# Power_Amp_carlos.net
KiCad netlist of a schematic drawn in EAGLE
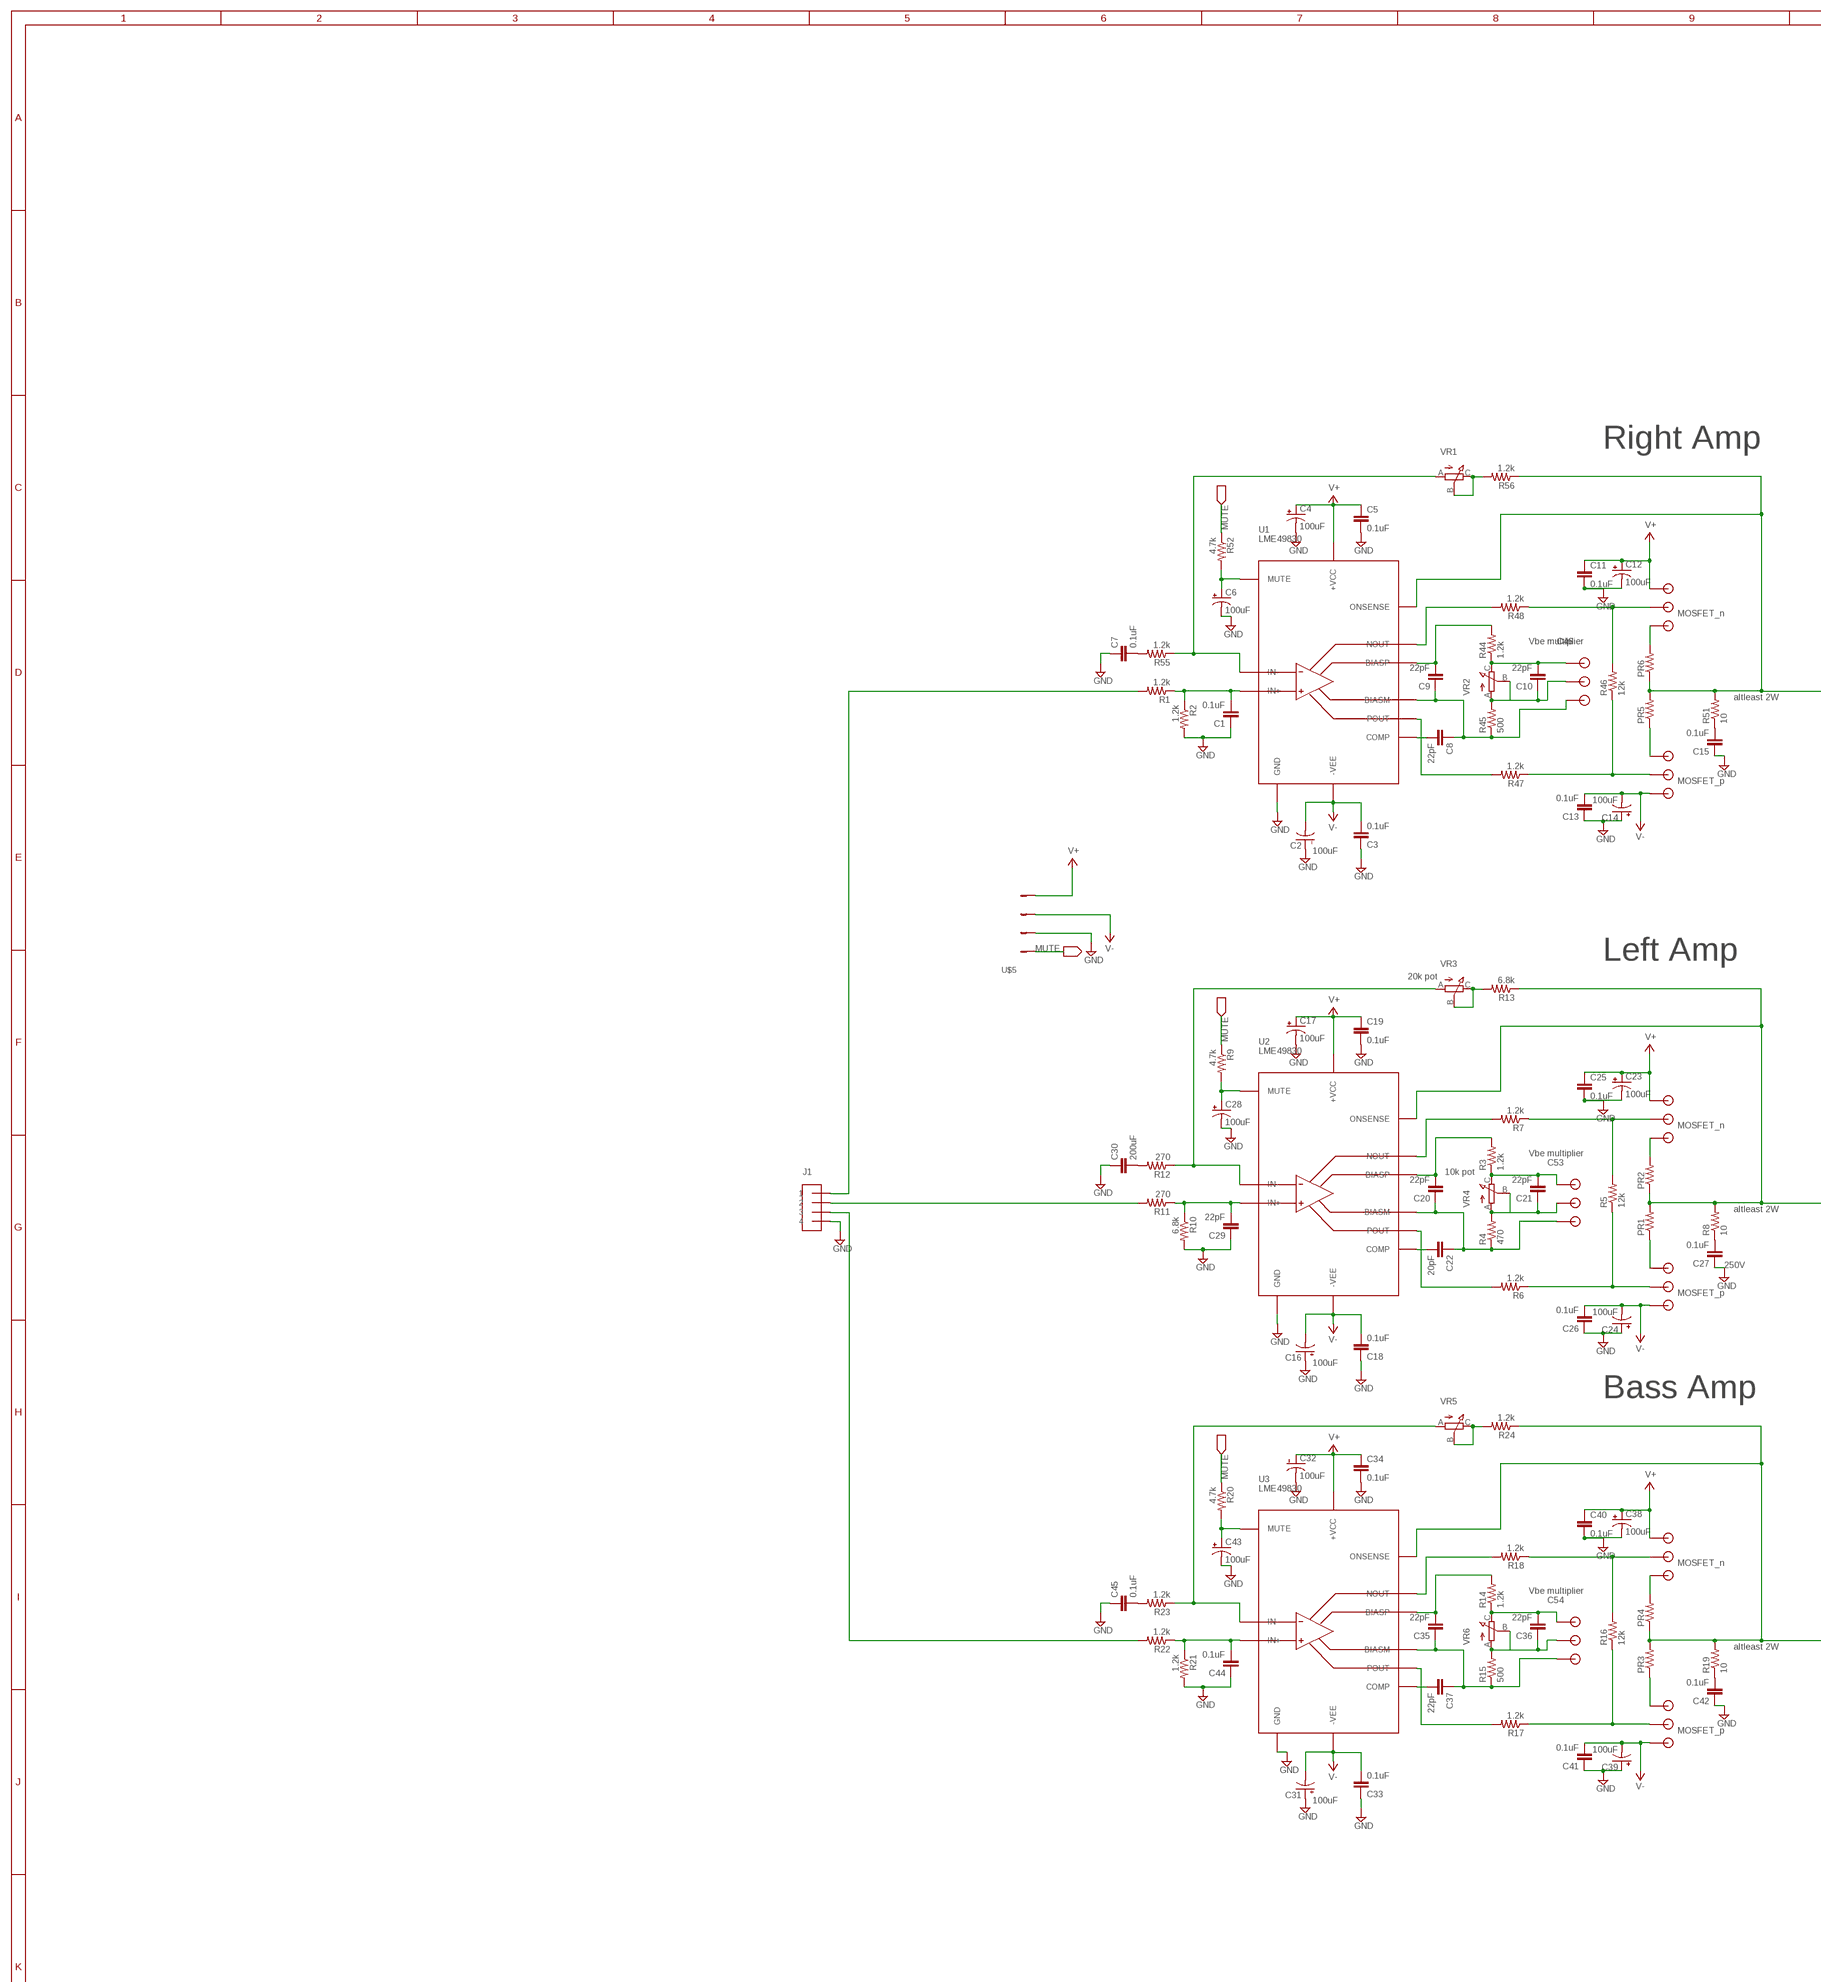
[diagram p0: schematic, sheet 1, part 1 of 3]
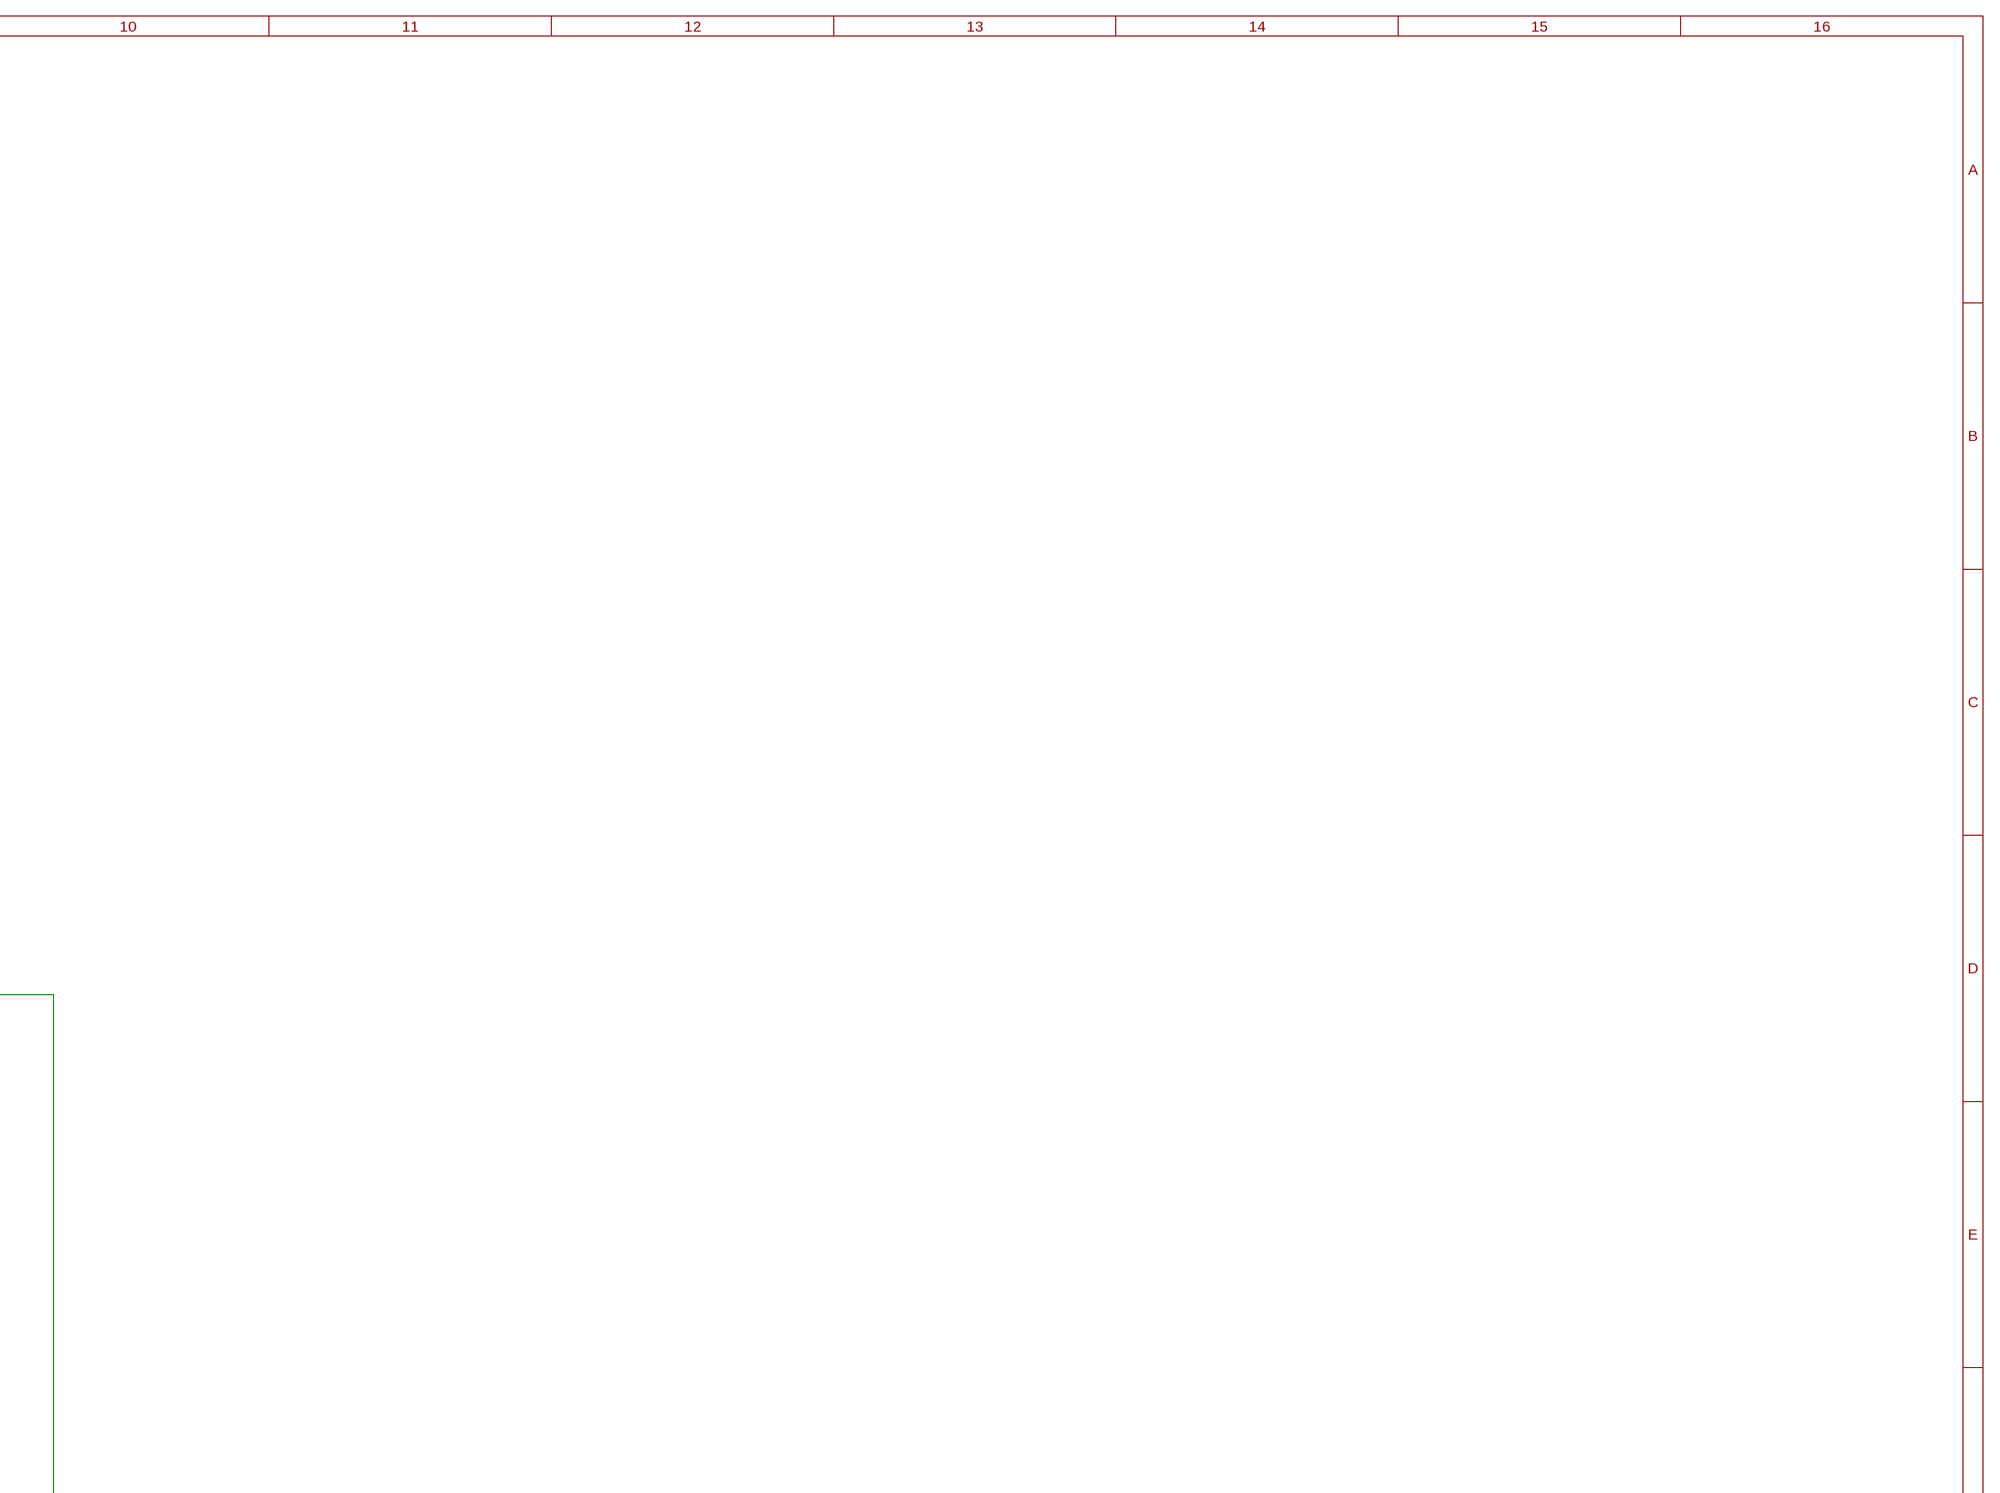
[diagram p1: schematic, sheet 1, part 2 of 3]
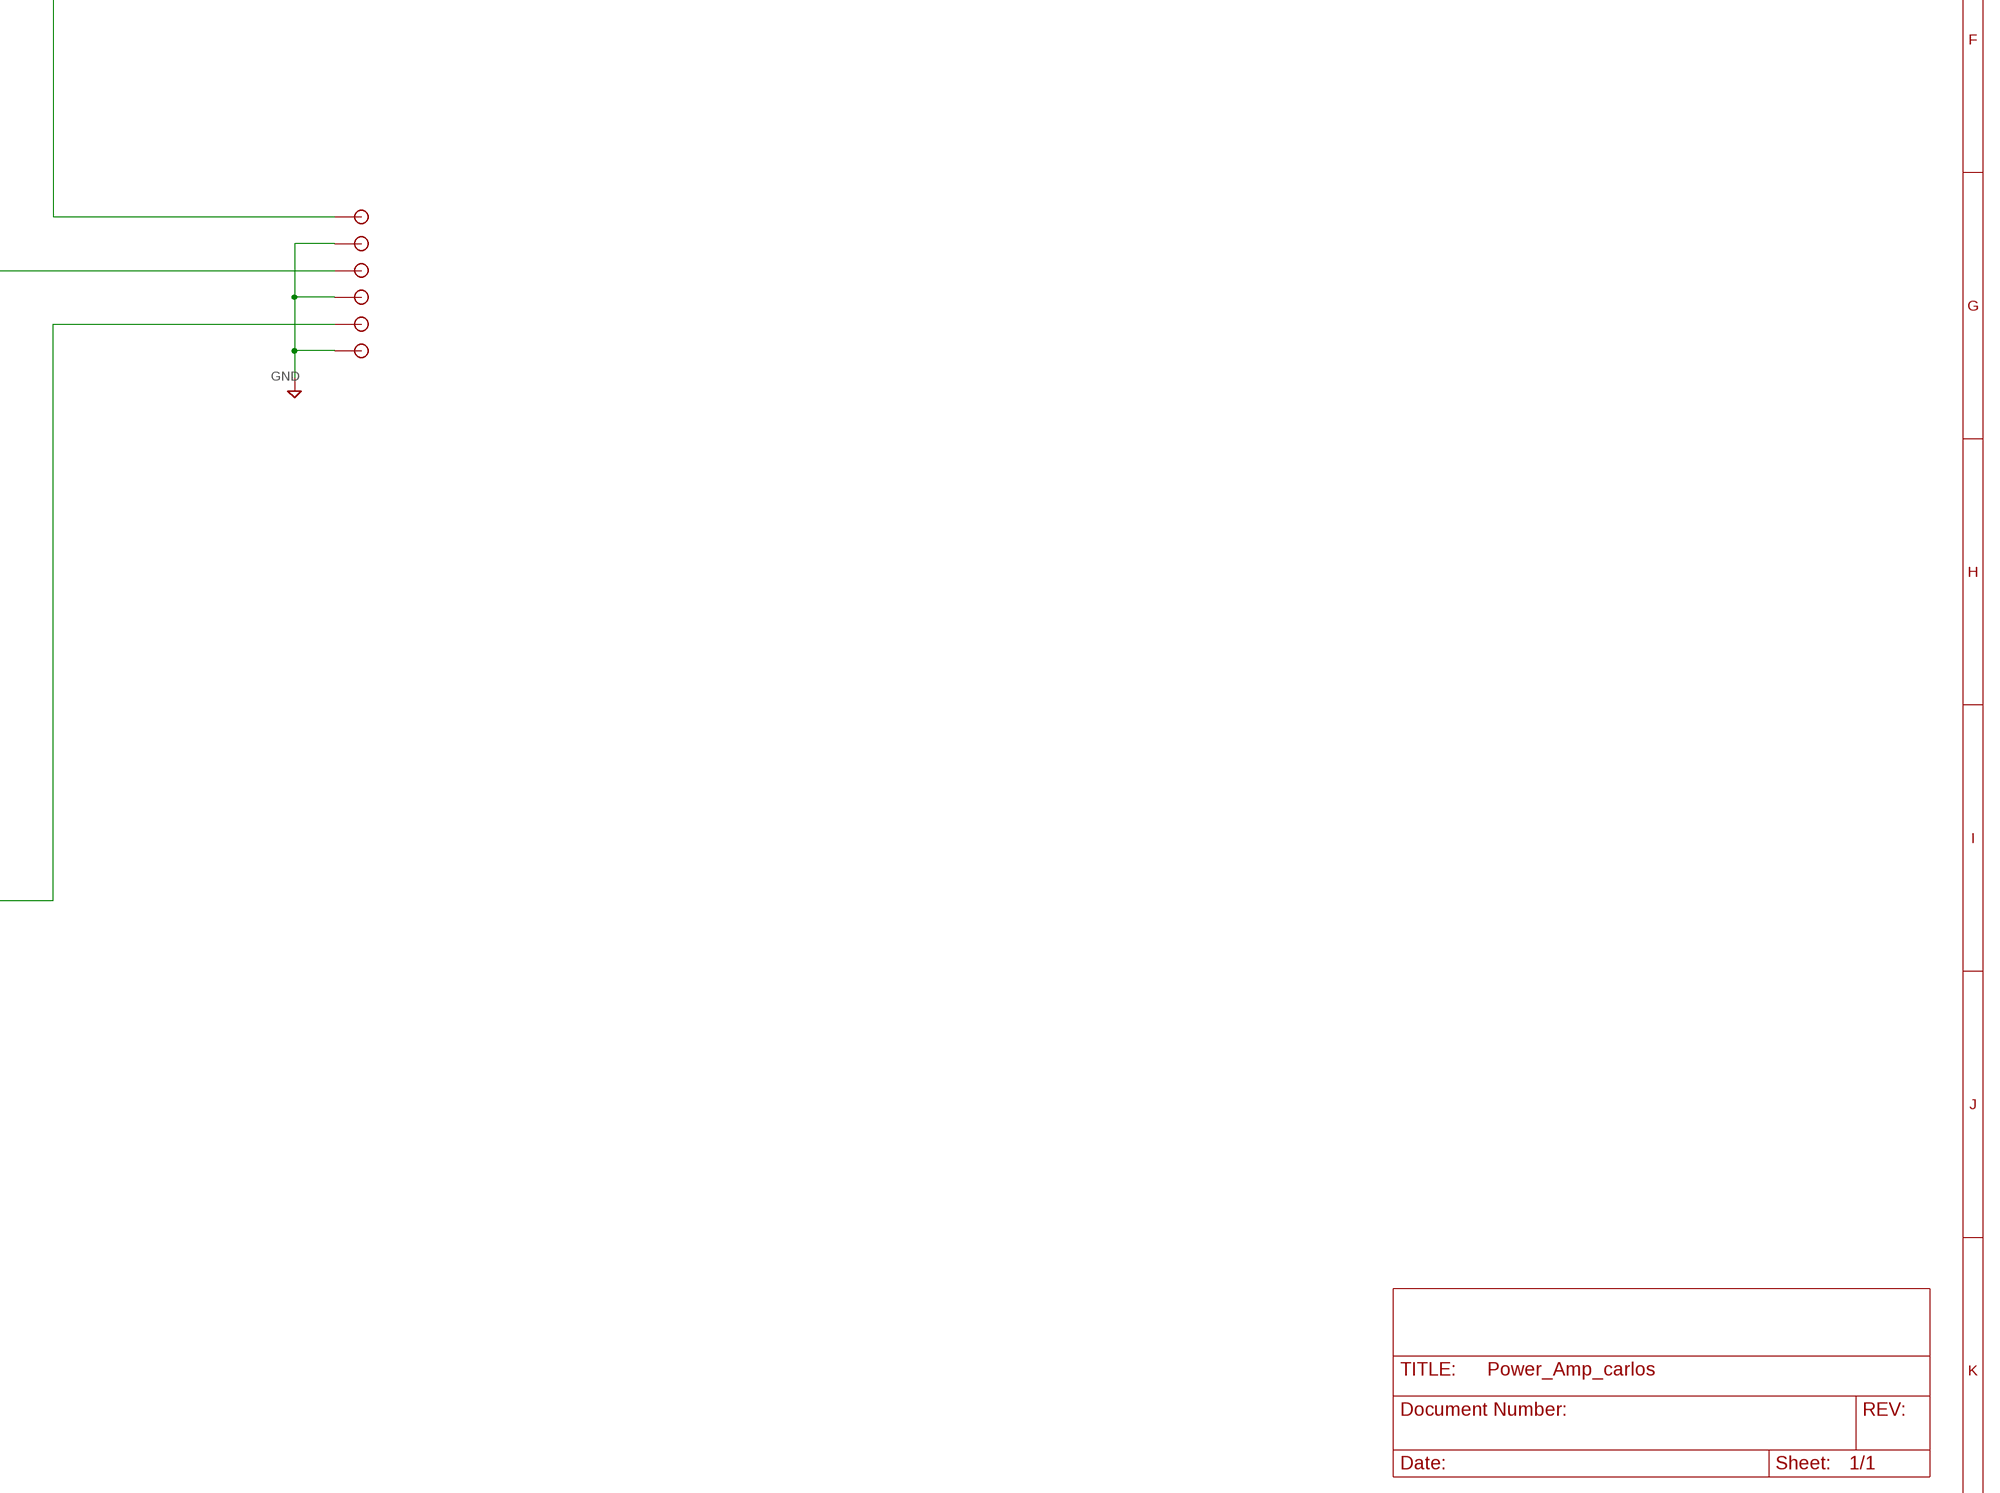
[diagram p2: schematic, sheet 1, part 3 of 3]

(export (version "E")
  (design (tool "Eeschema 10.0.6"))
  (components
    (comp (ref "C1")
      (value "0.1uF")
      (footprint "eagle-import:C050-024X044")
      (libsource (lib "eagle-import") (part "C-EU050-024X044"))
    )
    (comp (ref "C2")
      (value "100uF")
      (footprint "eagle-import:E2,5-6")
      (libsource (lib "eagle-import") (part "CPOL-USE2.5-6"))
    )
    (comp (ref "C3")
      (value "0.1uF")
      (footprint "eagle-import:C050-024X044")
      (libsource (lib "eagle-import") (part "C-EU050-024X044"))
    )
    (comp (ref "C4")
      (value "100uF")
      (footprint "eagle-import:E2,5-6")
      (libsource (lib "eagle-import") (part "CPOL-USE2.5-6"))
    )
    (comp (ref "C5")
      (value "0.1uF")
      (footprint "eagle-import:C050-024X044")
      (libsource (lib "eagle-import") (part "C-EU050-024X044"))
    )
    (comp (ref "C6")
      (value "100uF")
      (footprint "eagle-import:E2,5-6")
      (libsource (lib "eagle-import") (part "CPOL-USE2.5-6"))
    )
    (comp (ref "C7")
      (value "0.1uF")
      (footprint "eagle-import:C050-024X044")
      (libsource (lib "eagle-import") (part "C-EU050-024X044"))
    )
    (comp (ref "C8")
      (value "22pF")
      (footprint "eagle-import:C050-024X044")
      (libsource (lib "eagle-import") (part "C-EU050-024X044"))
    )
    (comp (ref "C9")
      (value "22pF")
      (footprint "eagle-import:C050-024X044")
      (libsource (lib "eagle-import") (part "C-EU050-024X044"))
    )
    (comp (ref "C10")
      (value "22pF")
      (footprint "eagle-import:C050-024X044")
      (libsource (lib "eagle-import") (part "C-EU050-024X044"))
    )
    (comp (ref "C11")
      (value "0.1uF")
      (footprint "eagle-import:C050-024X044")
      (libsource (lib "eagle-import") (part "C-EU050-024X044"))
    )
    (comp (ref "C12")
      (value "100uF")
      (footprint "eagle-import:E2,5-6")
      (libsource (lib "eagle-import") (part "CPOL-USE2.5-6"))
    )
    (comp (ref "C13")
      (value "0.1uF")
      (footprint "eagle-import:C050-024X044")
      (libsource (lib "eagle-import") (part "C-EU050-024X044"))
    )
    (comp (ref "C14")
      (value "100uF")
      (footprint "eagle-import:E2,5-6")
      (libsource (lib "eagle-import") (part "CPOL-USE2.5-6"))
    )
    (comp (ref "C15")
      (value "0.1uF")
      (footprint "eagle-import:C050-024X044")
      (libsource (lib "eagle-import") (part "C-EU050-024X044"))
    )
    (comp (ref "C16")
      (value "100uF")
      (footprint "eagle-import:E2,5-6")
      (libsource (lib "eagle-import") (part "CPOL-USE2.5-6"))
    )
    (comp (ref "C17")
      (value "100uF")
      (footprint "eagle-import:E2,5-6")
      (libsource (lib "eagle-import") (part "CPOL-USE2.5-6"))
    )
    (comp (ref "C18")
      (value "0.1uF")
      (footprint "eagle-import:C050-024X044")
      (libsource (lib "eagle-import") (part "C-EU050-024X044"))
    )
    (comp (ref "C19")
      (value "0.1uF")
      (footprint "eagle-import:C050-024X044")
      (libsource (lib "eagle-import") (part "C-EU050-024X044"))
    )
    (comp (ref "C20")
      (value "22pF")
      (footprint "eagle-import:C050-024X044")
      (libsource (lib "eagle-import") (part "C-EU050-024X044"))
    )
    (comp (ref "C21")
      (value "22pF")
      (footprint "eagle-import:C050-024X044")
      (libsource (lib "eagle-import") (part "C-EU050-024X044"))
    )
    (comp (ref "C22")
      (value "20pF")
      (footprint "eagle-import:C050-024X044")
      (libsource (lib "eagle-import") (part "C-EU050-024X044"))
    )
    (comp (ref "C23")
      (value "100uF")
      (footprint "eagle-import:E2,5-6")
      (libsource (lib "eagle-import") (part "CPOL-USE2.5-6"))
    )
    (comp (ref "C24")
      (value "100uF")
      (footprint "eagle-import:E2,5-6")
      (libsource (lib "eagle-import") (part "CPOL-USE2.5-6"))
    )
    (comp (ref "C25")
      (value "0.1uF")
      (footprint "eagle-import:C050-024X044")
      (libsource (lib "eagle-import") (part "C-EU050-024X044"))
    )
    (comp (ref "C26")
      (value "0.1uF")
      (footprint "eagle-import:C050-024X044")
      (libsource (lib "eagle-import") (part "C-EU050-024X044"))
    )
    (comp (ref "C27")
      (value "0.1uF")
      (footprint "eagle-import:C050-024X044")
      (libsource (lib "eagle-import") (part "C-EU050-024X044"))
    )
    (comp (ref "C28")
      (value "100uF")
      (footprint "eagle-import:E2,5-6")
      (libsource (lib "eagle-import") (part "CPOL-USE2.5-6"))
    )
    (comp (ref "C29")
      (value "22pF")
      (footprint "eagle-import:C050-024X044")
      (libsource (lib "eagle-import") (part "C-EU050-024X044"))
    )
    (comp (ref "C30")
      (value "200uF")
      (footprint "eagle-import:C050-024X044")
      (libsource (lib "eagle-import") (part "C-EU050-024X044"))
    )
    (comp (ref "C31")
      (value "100uF")
      (footprint "eagle-import:E2,5-6")
      (libsource (lib "eagle-import") (part "CPOL-USE2.5-6"))
    )
    (comp (ref "C32")
      (value "100uF")
      (footprint "eagle-import:E2,5-6")
      (libsource (lib "eagle-import") (part "CPOL-USE2.5-6"))
    )
    (comp (ref "C33")
      (value "0.1uF")
      (footprint "eagle-import:C050-024X044")
      (libsource (lib "eagle-import") (part "C-EU050-024X044"))
    )
    (comp (ref "C34")
      (value "0.1uF")
      (footprint "eagle-import:C050-024X044")
      (libsource (lib "eagle-import") (part "C-EU050-024X044"))
    )
    (comp (ref "C35")
      (value "22pF")
      (footprint "eagle-import:C050-024X044")
      (libsource (lib "eagle-import") (part "C-EU050-024X044"))
    )
    (comp (ref "C36")
      (value "22pF")
      (footprint "eagle-import:C050-024X044")
      (libsource (lib "eagle-import") (part "C-EU050-024X044"))
    )
    (comp (ref "C37")
      (value "22pF")
      (footprint "eagle-import:C050-024X044")
      (libsource (lib "eagle-import") (part "C-EU050-024X044"))
    )
    (comp (ref "C38")
      (value "100uF")
      (footprint "eagle-import:E2,5-6")
      (libsource (lib "eagle-import") (part "CPOL-USE2.5-6"))
    )
    (comp (ref "C39")
      (value "100uF")
      (footprint "eagle-import:E2,5-6")
      (libsource (lib "eagle-import") (part "CPOL-USE2.5-6"))
    )
    (comp (ref "C40")
      (value "0.1uF")
      (footprint "eagle-import:C050-024X044")
      (libsource (lib "eagle-import") (part "C-EU050-024X044"))
    )
    (comp (ref "C41")
      (value "0.1uF")
      (footprint "eagle-import:C050-024X044")
      (libsource (lib "eagle-import") (part "C-EU050-024X044"))
    )
    (comp (ref "C42")
      (value "0.1uF")
      (footprint "eagle-import:C050-024X044")
      (libsource (lib "eagle-import") (part "C-EU050-024X044"))
    )
    (comp (ref "C43")
      (value "100uF")
      (footprint "eagle-import:E2,5-6")
      (libsource (lib "eagle-import") (part "CPOL-USE2.5-6"))
    )
    (comp (ref "C44")
      (value "0.1uF")
      (footprint "eagle-import:C050-024X044")
      (libsource (lib "eagle-import") (part "C-EU050-024X044"))
    )
    (comp (ref "C45")
      (value "0.1uF")
      (footprint "eagle-import:C050-024X044")
      (libsource (lib "eagle-import") (part "C-EU050-024X044"))
    )
    (comp (ref "C46")
      (value "OSTVN03A150")
      (footprint "eagle-import:OSTVN03A150")
      (libsource (lib "eagle-import") (part "OSTVN03A150"))
    )
    (comp (ref "C47")
      (value "1984620")
      (footprint "eagle-import:1984620")
      (libsource (lib "eagle-import") (part "1984620"))
    )
    (comp (ref "C48")
      (value "1984620")
      (footprint "eagle-import:1984620")
      (libsource (lib "eagle-import") (part "1984620"))
    )
    (comp (ref "C49")
      (value "1984620")
      (footprint "eagle-import:1984620")
      (libsource (lib "eagle-import") (part "1984620"))
    )
    (comp (ref "C50")
      (value "1984620")
      (footprint "eagle-import:1984620")
      (libsource (lib "eagle-import") (part "1984620"))
    )
    (comp (ref "C51")
      (value "1984620")
      (footprint "eagle-import:1984620")
      (libsource (lib "eagle-import") (part "1984620"))
    )
    (comp (ref "C52")
      (value "1984620")
      (footprint "eagle-import:1984620")
      (libsource (lib "eagle-import") (part "1984620"))
    )
    (comp (ref "C53")
      (value "OSTVN03A150")
      (footprint "eagle-import:OSTVN03A150")
      (libsource (lib "eagle-import") (part "OSTVN03A150"))
    )
    (comp (ref "C54")
      (value "OSTVN03A150")
      (footprint "eagle-import:OSTVN03A150")
      (libsource (lib "eagle-import") (part "OSTVN03A150"))
    )
    (comp (ref "C55")
      (value "1984659")
      (footprint "eagle-import:1984659")
      (libsource (lib "eagle-import") (part "1984659"))
    )
    (comp (ref "J1")
      (value "4_PIN_AMPCONN")
      (footprint "eagle-import:4_PIN_AMPCON")
      (libsource (lib "eagle-import") (part "4_PIN_AMPCONN"))
    )
    (comp (ref "PR1")
      (value "R-US_0617/5V")
      (footprint "eagle-import:0617V")
      (libsource (lib "eagle-import") (part "R-US_0617/5V"))
    )
    (comp (ref "PR2")
      (value "R-US_0617/5V")
      (footprint "eagle-import:0617V")
      (libsource (lib "eagle-import") (part "R-US_0617/5V"))
    )
    (comp (ref "PR3")
      (value "R-US_0617/5V")
      (footprint "eagle-import:0617V")
      (libsource (lib "eagle-import") (part "R-US_0617/5V"))
    )
    (comp (ref "PR4")
      (value "R-US_0617/5V")
      (footprint "eagle-import:0617V")
      (libsource (lib "eagle-import") (part "R-US_0617/5V"))
    )
    (comp (ref "PR5")
      (value "R-US_0617/5V")
      (footprint "eagle-import:0617V")
      (libsource (lib "eagle-import") (part "R-US_0617/5V"))
    )
    (comp (ref "PR6")
      (value "R-US_0617/5V")
      (footprint "eagle-import:0617V")
      (libsource (lib "eagle-import") (part "R-US_0617/5V"))
    )
    (comp (ref "R1")
      (value "1.2k")
      (footprint "eagle-import:0204V")
      (libsource (lib "eagle-import") (part "R-US_0204/2V"))
    )
    (comp (ref "R2")
      (value "1.2k")
      (footprint "eagle-import:0204V")
      (libsource (lib "eagle-import") (part "R-US_0204/2V"))
    )
    (comp (ref "R3")
      (value "1.2k")
      (footprint "eagle-import:0204V")
      (libsource (lib "eagle-import") (part "R-US_0204/2V"))
    )
    (comp (ref "R4")
      (value "470")
      (footprint "eagle-import:0204V")
      (libsource (lib "eagle-import") (part "R-US_0204/2V"))
    )
    (comp (ref "R5")
      (value "12k")
      (footprint "eagle-import:0204V")
      (libsource (lib "eagle-import") (part "R-US_0204/2V"))
    )
    (comp (ref "R6")
      (value "1.2k")
      (footprint "eagle-import:0204V")
      (libsource (lib "eagle-import") (part "R-US_0204/2V"))
    )
    (comp (ref "R7")
      (value "1.2k")
      (footprint "eagle-import:0204V")
      (libsource (lib "eagle-import") (part "R-US_0204/2V"))
    )
    (comp (ref "R8")
      (value "10")
      (footprint "eagle-import:0617V")
      (libsource (lib "eagle-import") (part "R-US_0617/5V"))
    )
    (comp (ref "R9")
      (value "4.7k")
      (footprint "eagle-import:0204V")
      (libsource (lib "eagle-import") (part "R-US_0204/2V"))
    )
    (comp (ref "R10")
      (value "6.8k")
      (footprint "eagle-import:0204V")
      (libsource (lib "eagle-import") (part "R-US_0204/2V"))
    )
    (comp (ref "R11")
      (value "270")
      (footprint "eagle-import:0204V")
      (libsource (lib "eagle-import") (part "R-US_0204/2V"))
    )
    (comp (ref "R12")
      (value "270")
      (footprint "eagle-import:0204V")
      (libsource (lib "eagle-import") (part "R-US_0204/2V"))
    )
    (comp (ref "R13")
      (value "6.8k")
      (footprint "eagle-import:0204V")
      (libsource (lib "eagle-import") (part "R-US_0204/2V"))
    )
    (comp (ref "R14")
      (value "1.2k")
      (footprint "eagle-import:0204V")
      (libsource (lib "eagle-import") (part "R-US_0204/2V"))
    )
    (comp (ref "R15")
      (value "500")
      (footprint "eagle-import:0204V")
      (libsource (lib "eagle-import") (part "R-US_0204/2V"))
    )
    (comp (ref "R16")
      (value "12k")
      (footprint "eagle-import:0204V")
      (libsource (lib "eagle-import") (part "R-US_0204/2V"))
    )
    (comp (ref "R17")
      (value "1.2k")
      (footprint "eagle-import:0204V")
      (libsource (lib "eagle-import") (part "R-US_0204/2V"))
    )
    (comp (ref "R18")
      (value "1.2k")
      (footprint "eagle-import:0204V")
      (libsource (lib "eagle-import") (part "R-US_0204/2V"))
    )
    (comp (ref "R19")
      (value "10")
      (footprint "eagle-import:0617V")
      (libsource (lib "eagle-import") (part "R-US_0617/5V"))
    )
    (comp (ref "R20")
      (value "4.7k")
      (footprint "eagle-import:0204V")
      (libsource (lib "eagle-import") (part "R-US_0204/2V"))
    )
    (comp (ref "R21")
      (value "1.2k")
      (footprint "eagle-import:0204V")
      (libsource (lib "eagle-import") (part "R-US_0204/2V"))
    )
    (comp (ref "R22")
      (value "1.2k")
      (footprint "eagle-import:0204V")
      (libsource (lib "eagle-import") (part "R-US_0204/2V"))
    )
    (comp (ref "R23")
      (value "1.2k")
      (footprint "eagle-import:0204V")
      (libsource (lib "eagle-import") (part "R-US_0204/2V"))
    )
    (comp (ref "R24")
      (value "1.2k")
      (footprint "eagle-import:0204V")
      (libsource (lib "eagle-import") (part "R-US_0204/2V"))
    )
    (comp (ref "R44")
      (value "1.2k")
      (footprint "eagle-import:0204V")
      (libsource (lib "eagle-import") (part "R-US_0204/2V"))
    )
    (comp (ref "R45")
      (value "500")
      (footprint "eagle-import:0204V")
      (libsource (lib "eagle-import") (part "R-US_0204/2V"))
    )
    (comp (ref "R46")
      (value "12k")
      (footprint "eagle-import:0204V")
      (libsource (lib "eagle-import") (part "R-US_0204/2V"))
    )
    (comp (ref "R47")
      (value "1.2k")
      (footprint "eagle-import:0204V")
      (libsource (lib "eagle-import") (part "R-US_0204/2V"))
    )
    (comp (ref "R48")
      (value "1.2k")
      (footprint "eagle-import:0204V")
      (libsource (lib "eagle-import") (part "R-US_0204/2V"))
    )
    (comp (ref "R51")
      (value "10")
      (footprint "eagle-import:0617V")
      (libsource (lib "eagle-import") (part "R-US_0617/5V"))
    )
    (comp (ref "R52")
      (value "4.7k")
      (footprint "eagle-import:0204V")
      (libsource (lib "eagle-import") (part "R-US_0204/2V"))
    )
    (comp (ref "R55")
      (value "1.2k")
      (footprint "eagle-import:0204V")
      (libsource (lib "eagle-import") (part "R-US_0204/2V"))
    )
    (comp (ref "R56")
      (value "1.2k")
      (footprint "eagle-import:0204V")
      (libsource (lib "eagle-import") (part "R-US_0204/2V"))
    )
    (comp (ref "U$5")
      (value "SCREW_TERMINAL_4")
      (footprint "eagle-import:SCREW_TERMINAL_4")
      (libsource (lib "eagle-import") (part "SCREW_TERMINAL_4"))
    )
    (comp (ref "U1")
      (value "LME49830")
      (footprint "eagle-import:NDN0015A")
      (libsource (lib "eagle-import") (part "LME49830"))
    )
    (comp (ref "U2")
      (value "LME49830")
      (footprint "eagle-import:NDN0015A")
      (libsource (lib "eagle-import") (part "LME49830"))
    )
    (comp (ref "U3")
      (value "LME49830")
      (footprint "eagle-import:NDN0015A")
      (libsource (lib "eagle-import") (part "LME49830"))
    )
    (comp (ref "VR1")
      (value "EVM2W")
      (footprint "eagle-import:EVM2W")
      (libsource (lib "eagle-import") (part "EVM2W"))
    )
    (comp (ref "VR2")
      (value "EVM2W")
      (footprint "eagle-import:EVM2W")
      (libsource (lib "eagle-import") (part "EVM2W"))
    )
    (comp (ref "VR3")
      (value "EVM2W")
      (footprint "eagle-import:EVM2W")
      (libsource (lib "eagle-import") (part "EVM2W"))
    )
    (comp (ref "VR4")
      (value "EVM2W")
      (footprint "eagle-import:EVM2W")
      (libsource (lib "eagle-import") (part "EVM2W"))
    )
    (comp (ref "VR5")
      (value "EVM2W")
      (footprint "eagle-import:EVM2W")
      (libsource (lib "eagle-import") (part "EVM2W"))
    )
    (comp (ref "VR6")
      (value "EVM2W")
      (footprint "eagle-import:EVM2W")
      (libsource (lib "eagle-import") (part "EVM2W"))
    )
  )
  (nets
    (net (code "1") (name "/MUTE") (class "Default")
      (node (ref "R20") (pin "1") (pinfunction "1_1") (pintype "passive"))
      (node (ref "R52") (pin "1") (pinfunction "1_1") (pintype "passive"))
      (node (ref "R9") (pin "1") (pinfunction "1_1") (pintype "passive"))
      (node (ref "U$5") (pin "1") (pinfunction "S1_1") (pintype "passive"))
    )
    (net (code "2") (name "GND") (class "Default")
      (node (ref "C1") (pin "1") (pinfunction "1_1") (pintype "passive"))
      (node (ref "C11") (pin "2") (pinfunction "2_2") (pintype "passive"))
      (node (ref "C12") (pin "-") (pinfunction "-_-") (pintype "passive"))
      (node (ref "C13") (pin "1") (pinfunction "1_1") (pintype "passive"))
      (node (ref "C14") (pin "+") (pinfunction "+_+") (pintype "passive"))
      (node (ref "C15") (pin "1") (pinfunction "1_1") (pintype "passive"))
      (node (ref "C16") (pin "+") (pinfunction "+_+") (pintype "passive"))
      (node (ref "C17") (pin "-") (pinfunction "-_-") (pintype "passive"))
      (node (ref "C18") (pin "1") (pinfunction "1_1") (pintype "passive"))
      (node (ref "C19") (pin "2") (pinfunction "2_2") (pintype "passive"))
      (node (ref "C2") (pin "+") (pinfunction "+_+") (pintype "passive"))
      (node (ref "C23") (pin "-") (pinfunction "-_-") (pintype "passive"))
      (node (ref "C24") (pin "+") (pinfunction "+_+") (pintype "passive"))
      (node (ref "C25") (pin "2") (pinfunction "2_2") (pintype "passive"))
      (node (ref "C26") (pin "1") (pinfunction "1_1") (pintype "passive"))
      (node (ref "C27") (pin "1") (pinfunction "1_1") (pintype "passive"))
      (node (ref "C28") (pin "-") (pinfunction "-_-") (pintype "passive"))
      (node (ref "C29") (pin "1") (pinfunction "1_1") (pintype "passive"))
      (node (ref "C3") (pin "1") (pinfunction "1_1") (pintype "passive"))
      (node (ref "C30") (pin "1") (pinfunction "1_1") (pintype "passive"))
      (node (ref "C31") (pin "+") (pinfunction "+_+") (pintype "passive"))
      (node (ref "C32") (pin "-") (pinfunction "-_-") (pintype "passive"))
      (node (ref "C33") (pin "1") (pinfunction "1_1") (pintype "passive"))
      (node (ref "C34") (pin "2") (pinfunction "2_2") (pintype "passive"))
      (node (ref "C38") (pin "-") (pinfunction "-_-") (pintype "passive"))
      (node (ref "C39") (pin "+") (pinfunction "+_+") (pintype "passive"))
      (node (ref "C4") (pin "-") (pinfunction "-_-") (pintype "passive"))
      (node (ref "C40") (pin "2") (pinfunction "2_2") (pintype "passive"))
      (node (ref "C41") (pin "1") (pinfunction "1_1") (pintype "passive"))
      (node (ref "C42") (pin "1") (pinfunction "1_1") (pintype "passive"))
      (node (ref "C43") (pin "-") (pinfunction "-_-") (pintype "passive"))
      (node (ref "C44") (pin "1") (pinfunction "1_1") (pintype "passive"))
      (node (ref "C45") (pin "1") (pinfunction "1_1") (pintype "passive"))
      (node (ref "C5") (pin "2") (pinfunction "2_2") (pintype "passive"))
      (node (ref "C55") (pin "P$2") (pinfunction "2_P$2") (pintype "bidirectional"))
      (node (ref "C55") (pin "P$4") (pinfunction "4_P$4") (pintype "bidirectional"))
      (node (ref "C55") (pin "P$6") (pinfunction "6_P$6") (pintype "bidirectional"))
      (node (ref "C6") (pin "-") (pinfunction "-_-") (pintype "passive"))
      (node (ref "C7") (pin "1") (pinfunction "1_1") (pintype "passive"))
      (node (ref "J1") (pin "4") (pinfunction "4_4") (pintype "passive"))
      (node (ref "R10") (pin "2") (pinfunction "2_2") (pintype "passive"))
      (node (ref "R2") (pin "2") (pinfunction "2_2") (pintype "passive"))
      (node (ref "R21") (pin "2") (pinfunction "2_2") (pintype "passive"))
      (node (ref "U$5") (pin "2") (pinfunction "S2_2") (pintype "passive"))
      (node (ref "U1") (pin "P3") (pinfunction "GND_P3") (pintype "bidirectional"))
      (node (ref "U2") (pin "P3") (pinfunction "GND_P3") (pintype "bidirectional"))
      (node (ref "U3") (pin "P3") (pinfunction "GND_P3") (pintype "bidirectional"))
    )
    (net (code "3") (name "Net-(C7-Pad2)") (class "Default")
      (node (ref "C7") (pin "2") (pinfunction "2_2") (pintype "passive"))
      (node (ref "R55") (pin "2") (pinfunction "2_2") (pintype "passive"))
    )
    (net (code "4") (name "Net-(C15-Pad2)") (class "Default")
      (node (ref "C15") (pin "2") (pinfunction "2_2") (pintype "passive"))
      (node (ref "R51") (pin "1") (pinfunction "1_1") (pintype "passive"))
    )
    (net (code "5") (name "Net-(C27-Pad2)") (class "Default")
      (node (ref "C27") (pin "2") (pinfunction "2_2") (pintype "passive"))
      (node (ref "R8") (pin "1") (pinfunction "1_1") (pintype "passive"))
    )
    (net (code "6") (name "Net-(C30-Pad2)") (class "Default")
      (node (ref "C30") (pin "2") (pinfunction "2_2") (pintype "passive"))
      (node (ref "R12") (pin "2") (pinfunction "2_2") (pintype "passive"))
    )
    (net (code "7") (name "Net-(C42-Pad2)") (class "Default")
      (node (ref "C42") (pin "2") (pinfunction "2_2") (pintype "passive"))
      (node (ref "R19") (pin "1") (pinfunction "1_1") (pintype "passive"))
    )
    (net (code "8") (name "Net-(C45-Pad2)") (class "Default")
      (node (ref "C45") (pin "2") (pinfunction "2_2") (pintype "passive"))
      (node (ref "R23") (pin "2") (pinfunction "2_2") (pintype "passive"))
    )
    (net (code "9") (name "Net-(C46-1)") (class "Default")
      (node (ref "C10") (pin "2") (pinfunction "2_2") (pintype "passive"))
      (node (ref "C46") (pin "P$1") (pinfunction "1_P$1") (pintype "bidirectional"))
      (node (ref "R44") (pin "1") (pinfunction "1_1") (pintype "passive"))
      (node (ref "VR2") (pin "C") (pinfunction "C_C") (pintype "passive"))
    )
    (net (code "10") (name "Net-(C46-2)") (class "Default")
      (node (ref "C10") (pin "1") (pinfunction "1_1") (pintype "passive"))
      (node (ref "C46") (pin "P$2") (pinfunction "2_P$2") (pintype "bidirectional"))
      (node (ref "R45") (pin "2") (pinfunction "2_2") (pintype "passive"))
      (node (ref "VR2") (pin "A") (pinfunction "A_A") (pintype "passive"))
      (node (ref "VR2") (pin "B") (pinfunction "B_B") (pintype "passive"))
    )
    (net (code "11") (name "Net-(C46-3)") (class "Default")
      (node (ref "C46") (pin "P$3") (pinfunction "3_P$3") (pintype "bidirectional"))
      (node (ref "C8") (pin "1") (pinfunction "1_1") (pintype "passive"))
      (node (ref "C9") (pin "1") (pinfunction "1_1") (pintype "passive"))
      (node (ref "R45") (pin "1") (pinfunction "1_1") (pintype "passive"))
      (node (ref "U1") (pin "P11") (pinfunction "BIASM_P11") (pintype "bidirectional"))
    )
    (net (code "12") (name "Net-(C47-2)") (class "Default")
      (node (ref "C47") (pin "P$2") (pinfunction "2_P$2") (pintype "bidirectional"))
      (node (ref "R46") (pin "2") (pinfunction "2_2") (pintype "passive"))
      (node (ref "R48") (pin "1") (pinfunction "1_1") (pintype "passive"))
    )
    (net (code "13") (name "Net-(C47-3)") (class "Default")
      (node (ref "C47") (pin "P$3") (pinfunction "3_P$3") (pintype "bidirectional"))
      (node (ref "PR6") (pin "2") (pinfunction "2_2") (pintype "passive"))
    )
    (net (code "14") (name "Net-(C48-1)") (class "Default")
      (node (ref "C48") (pin "P$1") (pinfunction "1_P$1") (pintype "bidirectional"))
      (node (ref "PR5") (pin "1") (pinfunction "1_1") (pintype "passive"))
    )
    (net (code "15") (name "Net-(C48-2)") (class "Default")
      (node (ref "C48") (pin "P$2") (pinfunction "2_P$2") (pintype "bidirectional"))
      (node (ref "R46") (pin "1") (pinfunction "1_1") (pintype "passive"))
      (node (ref "R47") (pin "1") (pinfunction "1_1") (pintype "passive"))
    )
    (net (code "16") (name "Net-(C49-1)") (class "Default")
      (node (ref "C49") (pin "P$1") (pinfunction "1_P$1") (pintype "bidirectional"))
      (node (ref "PR1") (pin "1") (pinfunction "1_1") (pintype "passive"))
    )
    (net (code "17") (name "Net-(C49-2)") (class "Default")
      (node (ref "C49") (pin "P$2") (pinfunction "2_P$2") (pintype "bidirectional"))
      (node (ref "R5") (pin "1") (pinfunction "1_1") (pintype "passive"))
      (node (ref "R6") (pin "1") (pinfunction "1_1") (pintype "passive"))
    )
    (net (code "18") (name "Net-(C50-2)") (class "Default")
      (node (ref "C50") (pin "P$2") (pinfunction "2_P$2") (pintype "bidirectional"))
      (node (ref "R5") (pin "2") (pinfunction "2_2") (pintype "passive"))
      (node (ref "R7") (pin "1") (pinfunction "1_1") (pintype "passive"))
    )
    (net (code "19") (name "Net-(C50-3)") (class "Default")
      (node (ref "C50") (pin "P$3") (pinfunction "3_P$3") (pintype "bidirectional"))
      (node (ref "PR2") (pin "2") (pinfunction "2_2") (pintype "passive"))
    )
    (net (code "20") (name "Net-(C51-2)") (class "Default")
      (node (ref "C51") (pin "P$2") (pinfunction "2_P$2") (pintype "bidirectional"))
      (node (ref "R16") (pin "2") (pinfunction "2_2") (pintype "passive"))
      (node (ref "R18") (pin "1") (pinfunction "1_1") (pintype "passive"))
    )
    (net (code "21") (name "Net-(C51-3)") (class "Default")
      (node (ref "C51") (pin "P$3") (pinfunction "3_P$3") (pintype "bidirectional"))
      (node (ref "PR4") (pin "2") (pinfunction "2_2") (pintype "passive"))
    )
    (net (code "22") (name "Net-(C52-1)") (class "Default")
      (node (ref "C52") (pin "P$1") (pinfunction "1_P$1") (pintype "bidirectional"))
      (node (ref "PR3") (pin "1") (pinfunction "1_1") (pintype "passive"))
    )
    (net (code "23") (name "Net-(C52-2)") (class "Default")
      (node (ref "C52") (pin "P$2") (pinfunction "2_P$2") (pintype "bidirectional"))
      (node (ref "R16") (pin "1") (pinfunction "1_1") (pintype "passive"))
      (node (ref "R17") (pin "1") (pinfunction "1_1") (pintype "passive"))
    )
    (net (code "24") (name "Net-(C53-1)") (class "Default")
      (node (ref "C21") (pin "2") (pinfunction "2_2") (pintype "passive"))
      (node (ref "C53") (pin "P$1") (pinfunction "1_P$1") (pintype "bidirectional"))
      (node (ref "R3") (pin "1") (pinfunction "1_1") (pintype "passive"))
      (node (ref "VR4") (pin "C") (pinfunction "C_C") (pintype "passive"))
    )
    (net (code "25") (name "Net-(C53-2)") (class "Default")
      (node (ref "C21") (pin "1") (pinfunction "1_1") (pintype "passive"))
      (node (ref "C53") (pin "P$2") (pinfunction "2_P$2") (pintype "bidirectional"))
      (node (ref "R4") (pin "2") (pinfunction "2_2") (pintype "passive"))
      (node (ref "VR4") (pin "A") (pinfunction "A_A") (pintype "passive"))
      (node (ref "VR4") (pin "B") (pinfunction "B_B") (pintype "passive"))
    )
    (net (code "26") (name "Net-(C53-3)") (class "Default")
      (node (ref "C20") (pin "1") (pinfunction "1_1") (pintype "passive"))
      (node (ref "C22") (pin "1") (pinfunction "1_1") (pintype "passive"))
      (node (ref "C53") (pin "P$3") (pinfunction "3_P$3") (pintype "bidirectional"))
      (node (ref "R4") (pin "1") (pinfunction "1_1") (pintype "passive"))
      (node (ref "U2") (pin "P11") (pinfunction "BIASM_P11") (pintype "bidirectional"))
    )
    (net (code "27") (name "Net-(C54-1)") (class "Default")
      (node (ref "C36") (pin "2") (pinfunction "2_2") (pintype "passive"))
      (node (ref "C54") (pin "P$1") (pinfunction "1_P$1") (pintype "bidirectional"))
      (node (ref "R14") (pin "1") (pinfunction "1_1") (pintype "passive"))
      (node (ref "VR6") (pin "C") (pinfunction "C_C") (pintype "passive"))
    )
    (net (code "28") (name "Net-(C54-2)") (class "Default")
      (node (ref "C36") (pin "1") (pinfunction "1_1") (pintype "passive"))
      (node (ref "C54") (pin "P$2") (pinfunction "2_P$2") (pintype "bidirectional"))
      (node (ref "R15") (pin "2") (pinfunction "2_2") (pintype "passive"))
      (node (ref "VR6") (pin "A") (pinfunction "A_A") (pintype "passive"))
      (node (ref "VR6") (pin "B") (pinfunction "B_B") (pintype "passive"))
    )
    (net (code "29") (name "Net-(C54-3)") (class "Default")
      (node (ref "C35") (pin "1") (pinfunction "1_1") (pintype "passive"))
      (node (ref "C37") (pin "1") (pinfunction "1_1") (pintype "passive"))
      (node (ref "C54") (pin "P$3") (pinfunction "3_P$3") (pintype "bidirectional"))
      (node (ref "R15") (pin "1") (pinfunction "1_1") (pintype "passive"))
      (node (ref "U3") (pin "P11") (pinfunction "BIASM_P11") (pintype "bidirectional"))
    )
    (net (code "30") (name "Net-(C55-1)") (class "Default")
      (node (ref "C55") (pin "P$1") (pinfunction "1_P$1") (pintype "bidirectional"))
      (node (ref "PR5") (pin "2") (pinfunction "2_2") (pintype "passive"))
      (node (ref "PR6") (pin "1") (pinfunction "1_1") (pintype "passive"))
      (node (ref "R51") (pin "2") (pinfunction "2_2") (pintype "passive"))
      (node (ref "R56") (pin "1") (pinfunction "1_1") (pintype "passive"))
      (node (ref "U1") (pin "P$8") (pinfunction "ONSENSE_P$8") (pintype "bidirectional"))
    )
    (net (code "31") (name "Net-(C55-3)") (class "Default")
      (node (ref "C55") (pin "P$3") (pinfunction "3_P$3") (pintype "bidirectional"))
      (node (ref "PR1") (pin "2") (pinfunction "2_2") (pintype "passive"))
      (node (ref "PR2") (pin "1") (pinfunction "1_1") (pintype "passive"))
      (node (ref "R13") (pin "1") (pinfunction "1_1") (pintype "passive"))
      (node (ref "R8") (pin "2") (pinfunction "2_2") (pintype "passive"))
      (node (ref "U2") (pin "P$8") (pinfunction "ONSENSE_P$8") (pintype "bidirectional"))
    )
    (net (code "32") (name "Net-(C55-5)") (class "Default")
      (node (ref "C55") (pin "P$5") (pinfunction "5_P$5") (pintype "bidirectional"))
      (node (ref "PR3") (pin "2") (pinfunction "2_2") (pintype "passive"))
      (node (ref "PR4") (pin "1") (pinfunction "1_1") (pintype "passive"))
      (node (ref "R19") (pin "2") (pinfunction "2_2") (pintype "passive"))
      (node (ref "R24") (pin "1") (pinfunction "1_1") (pintype "passive"))
      (node (ref "U3") (pin "P$8") (pinfunction "ONSENSE_P$8") (pintype "bidirectional"))
    )
    (net (code "33") (name "Net-(J1-Pad1)") (class "Default")
      (node (ref "J1") (pin "1") (pinfunction "1_1") (pintype "passive"))
      (node (ref "R1") (pin "2") (pinfunction "2_2") (pintype "passive"))
    )
    (net (code "34") (name "Net-(J1-Pad2)") (class "Default")
      (node (ref "J1") (pin "2") (pinfunction "2_2") (pintype "passive"))
      (node (ref "R11") (pin "2") (pinfunction "2_2") (pintype "passive"))
    )
    (net (code "35") (name "Net-(J1-Pad3)") (class "Default")
      (node (ref "J1") (pin "3") (pinfunction "3_3") (pintype "passive"))
      (node (ref "R22") (pin "2") (pinfunction "2_2") (pintype "passive"))
    )
    (net (code "36") (name "Net-(R13-Pad2)") (class "Default")
      (node (ref "R13") (pin "2") (pinfunction "2_2") (pintype "passive"))
      (node (ref "VR3") (pin "B") (pinfunction "B_B") (pintype "passive"))
      (node (ref "VR3") (pin "C") (pinfunction "C_C") (pintype "passive"))
    )
    (net (code "37") (name "Net-(R24-Pad2)") (class "Default")
      (node (ref "R24") (pin "2") (pinfunction "2_2") (pintype "passive"))
      (node (ref "VR5") (pin "B") (pinfunction "B_B") (pintype "passive"))
      (node (ref "VR5") (pin "C") (pinfunction "C_C") (pintype "passive"))
    )
    (net (code "38") (name "Net-(R56-Pad2)") (class "Default")
      (node (ref "R56") (pin "2") (pinfunction "2_2") (pintype "passive"))
      (node (ref "VR1") (pin "B") (pinfunction "B_B") (pintype "passive"))
      (node (ref "VR1") (pin "C") (pinfunction "C_C") (pintype "passive"))
    )
    (net (code "39") (name "Net-(U1-BIASP)") (class "Default")
      (node (ref "C9") (pin "2") (pinfunction "2_2") (pintype "passive"))
      (node (ref "R44") (pin "2") (pinfunction "2_2") (pintype "passive"))
      (node (ref "U1") (pin "P12") (pinfunction "BIASP_P12") (pintype "bidirectional"))
    )
    (net (code "40") (name "Net-(U1-COMP)") (class "Default")
      (node (ref "C8") (pin "2") (pinfunction "2_2") (pintype "passive"))
      (node (ref "U1") (pin "P6") (pinfunction "COMP_P6") (pintype "bidirectional"))
    )
    (net (code "41") (name "Net-(U1-IN+)") (class "Default")
      (node (ref "C1") (pin "2") (pinfunction "2_2") (pintype "passive"))
      (node (ref "R1") (pin "1") (pinfunction "1_1") (pintype "passive"))
      (node (ref "R2") (pin "1") (pinfunction "1_1") (pintype "passive"))
      (node (ref "U1") (pin "P4") (pinfunction "IN+_P4") (pintype "bidirectional"))
    )
    (net (code "42") (name "Net-(U1-IN-)") (class "Default")
      (node (ref "R55") (pin "1") (pinfunction "1_1") (pintype "passive"))
      (node (ref "U1") (pin "P5") (pinfunction "IN-_P5") (pintype "bidirectional"))
      (node (ref "VR1") (pin "A") (pinfunction "A_A") (pintype "passive"))
    )
    (net (code "43") (name "Net-(U1-MUTE)") (class "Default")
      (node (ref "C6") (pin "+") (pinfunction "+_+") (pintype "passive"))
      (node (ref "R52") (pin "2") (pinfunction "2_2") (pintype "passive"))
      (node (ref "U1") (pin "P2") (pinfunction "MUTE_P2") (pintype "bidirectional"))
    )
    (net (code "44") (name "Net-(U1-NOUT)") (class "Default")
      (node (ref "R48") (pin "2") (pinfunction "2_2") (pintype "passive"))
      (node (ref "U1") (pin "P14") (pinfunction "NOUT_P14") (pintype "bidirectional"))
    )
    (net (code "45") (name "Net-(U1-POUT)") (class "Default")
      (node (ref "R47") (pin "2") (pinfunction "2_2") (pintype "passive"))
      (node (ref "U1") (pin "P13") (pinfunction "POUT_P13") (pintype "bidirectional"))
    )
    (net (code "46") (name "Net-(U2-BIASP)") (class "Default")
      (node (ref "C20") (pin "2") (pinfunction "2_2") (pintype "passive"))
      (node (ref "R3") (pin "2") (pinfunction "2_2") (pintype "passive"))
      (node (ref "U2") (pin "P12") (pinfunction "BIASP_P12") (pintype "bidirectional"))
    )
    (net (code "47") (name "Net-(U2-COMP)") (class "Default")
      (node (ref "C22") (pin "2") (pinfunction "2_2") (pintype "passive"))
      (node (ref "U2") (pin "P6") (pinfunction "COMP_P6") (pintype "bidirectional"))
    )
    (net (code "48") (name "Net-(U2-IN+)") (class "Default")
      (node (ref "C29") (pin "2") (pinfunction "2_2") (pintype "passive"))
      (node (ref "R10") (pin "1") (pinfunction "1_1") (pintype "passive"))
      (node (ref "R11") (pin "1") (pinfunction "1_1") (pintype "passive"))
      (node (ref "U2") (pin "P4") (pinfunction "IN+_P4") (pintype "bidirectional"))
    )
    (net (code "49") (name "Net-(U2-IN-)") (class "Default")
      (node (ref "R12") (pin "1") (pinfunction "1_1") (pintype "passive"))
      (node (ref "U2") (pin "P5") (pinfunction "IN-_P5") (pintype "bidirectional"))
      (node (ref "VR3") (pin "A") (pinfunction "A_A") (pintype "passive"))
    )
    (net (code "50") (name "Net-(U2-MUTE)") (class "Default")
      (node (ref "C28") (pin "+") (pinfunction "+_+") (pintype "passive"))
      (node (ref "R9") (pin "2") (pinfunction "2_2") (pintype "passive"))
      (node (ref "U2") (pin "P2") (pinfunction "MUTE_P2") (pintype "bidirectional"))
    )
    (net (code "51") (name "Net-(U2-NOUT)") (class "Default")
      (node (ref "R7") (pin "2") (pinfunction "2_2") (pintype "passive"))
      (node (ref "U2") (pin "P14") (pinfunction "NOUT_P14") (pintype "bidirectional"))
    )
    (net (code "52") (name "Net-(U2-POUT)") (class "Default")
      (node (ref "R6") (pin "2") (pinfunction "2_2") (pintype "passive"))
      (node (ref "U2") (pin "P13") (pinfunction "POUT_P13") (pintype "bidirectional"))
    )
    (net (code "53") (name "Net-(U3-BIASP)") (class "Default")
      (node (ref "C35") (pin "2") (pinfunction "2_2") (pintype "passive"))
      (node (ref "R14") (pin "2") (pinfunction "2_2") (pintype "passive"))
      (node (ref "U3") (pin "P12") (pinfunction "BIASP_P12") (pintype "bidirectional"))
    )
    (net (code "54") (name "Net-(U3-COMP)") (class "Default")
      (node (ref "C37") (pin "2") (pinfunction "2_2") (pintype "passive"))
      (node (ref "U3") (pin "P6") (pinfunction "COMP_P6") (pintype "bidirectional"))
    )
    (net (code "55") (name "Net-(U3-IN+)") (class "Default")
      (node (ref "C44") (pin "2") (pinfunction "2_2") (pintype "passive"))
      (node (ref "R21") (pin "1") (pinfunction "1_1") (pintype "passive"))
      (node (ref "R22") (pin "1") (pinfunction "1_1") (pintype "passive"))
      (node (ref "U3") (pin "P4") (pinfunction "IN+_P4") (pintype "bidirectional"))
    )
    (net (code "56") (name "Net-(U3-IN-)") (class "Default")
      (node (ref "R23") (pin "1") (pinfunction "1_1") (pintype "passive"))
      (node (ref "U3") (pin "P5") (pinfunction "IN-_P5") (pintype "bidirectional"))
      (node (ref "VR5") (pin "A") (pinfunction "A_A") (pintype "passive"))
    )
    (net (code "57") (name "Net-(U3-MUTE)") (class "Default")
      (node (ref "C43") (pin "+") (pinfunction "+_+") (pintype "passive"))
      (node (ref "R20") (pin "2") (pinfunction "2_2") (pintype "passive"))
      (node (ref "U3") (pin "P2") (pinfunction "MUTE_P2") (pintype "bidirectional"))
    )
    (net (code "58") (name "Net-(U3-NOUT)") (class "Default")
      (node (ref "R18") (pin "2") (pinfunction "2_2") (pintype "passive"))
      (node (ref "U3") (pin "P14") (pinfunction "NOUT_P14") (pintype "bidirectional"))
    )
    (net (code "59") (name "Net-(U3-POUT)") (class "Default")
      (node (ref "R17") (pin "2") (pinfunction "2_2") (pintype "passive"))
      (node (ref "U3") (pin "P13") (pinfunction "POUT_P13") (pintype "bidirectional"))
    )
    (net (code "60") (name "V+") (class "Default")
      (node (ref "C11") (pin "1") (pinfunction "1_1") (pintype "passive"))
      (node (ref "C12") (pin "+") (pinfunction "+_+") (pintype "passive"))
      (node (ref "C17") (pin "+") (pinfunction "+_+") (pintype "passive"))
      (node (ref "C19") (pin "1") (pinfunction "1_1") (pintype "passive"))
      (node (ref "C23") (pin "+") (pinfunction "+_+") (pintype "passive"))
      (node (ref "C25") (pin "1") (pinfunction "1_1") (pintype "passive"))
      (node (ref "C32") (pin "+") (pinfunction "+_+") (pintype "passive"))
      (node (ref "C34") (pin "1") (pinfunction "1_1") (pintype "passive"))
      (node (ref "C38") (pin "+") (pinfunction "+_+") (pintype "passive"))
      (node (ref "C4") (pin "+") (pinfunction "+_+") (pintype "passive"))
      (node (ref "C40") (pin "1") (pinfunction "1_1") (pintype "passive"))
      (node (ref "C47") (pin "P$1") (pinfunction "1_P$1") (pintype "bidirectional"))
      (node (ref "C5") (pin "1") (pinfunction "1_1") (pintype "passive"))
      (node (ref "C50") (pin "P$1") (pinfunction "1_P$1") (pintype "bidirectional"))
      (node (ref "C51") (pin "P$1") (pinfunction "1_P$1") (pintype "bidirectional"))
      (node (ref "U$5") (pin "4") (pinfunction "S4_4") (pintype "passive"))
      (node (ref "U1") (pin "P15") (pinfunction "+VCC_P15") (pintype "passive"))
      (node (ref "U2") (pin "P15") (pinfunction "+VCC_P15") (pintype "passive"))
      (node (ref "U3") (pin "P15") (pinfunction "+VCC_P15") (pintype "passive"))
    )
    (net (code "61") (name "V-") (class "Default")
      (node (ref "C13") (pin "2") (pinfunction "2_2") (pintype "passive"))
      (node (ref "C14") (pin "-") (pinfunction "-_-") (pintype "passive"))
      (node (ref "C16") (pin "-") (pinfunction "-_-") (pintype "passive"))
      (node (ref "C18") (pin "2") (pinfunction "2_2") (pintype "passive"))
      (node (ref "C2") (pin "-") (pinfunction "-_-") (pintype "passive"))
      (node (ref "C24") (pin "-") (pinfunction "-_-") (pintype "passive"))
      (node (ref "C26") (pin "2") (pinfunction "2_2") (pintype "passive"))
      (node (ref "C3") (pin "2") (pinfunction "2_2") (pintype "passive"))
      (node (ref "C31") (pin "-") (pinfunction "-_-") (pintype "passive"))
      (node (ref "C33") (pin "2") (pinfunction "2_2") (pintype "passive"))
      (node (ref "C39") (pin "-") (pinfunction "-_-") (pintype "passive"))
      (node (ref "C41") (pin "2") (pinfunction "2_2") (pintype "passive"))
      (node (ref "C48") (pin "P$3") (pinfunction "3_P$3") (pintype "bidirectional"))
      (node (ref "C49") (pin "P$3") (pinfunction "3_P$3") (pintype "bidirectional"))
      (node (ref "C52") (pin "P$3") (pinfunction "3_P$3") (pintype "bidirectional"))
      (node (ref "U$5") (pin "3") (pinfunction "S3_3") (pintype "passive"))
      (node (ref "U1") (pin "P10") (pinfunction "-VEE_P10") (pintype "power_in"))
      (node (ref "U2") (pin "P10") (pinfunction "-VEE_P10") (pintype "power_in"))
      (node (ref "U3") (pin "P10") (pinfunction "-VEE_P10") (pintype "power_in"))
    )
  )
)
